# Battery_Charging_Circuit.net
KiCad netlist of a schematic drawn in Altium Designer
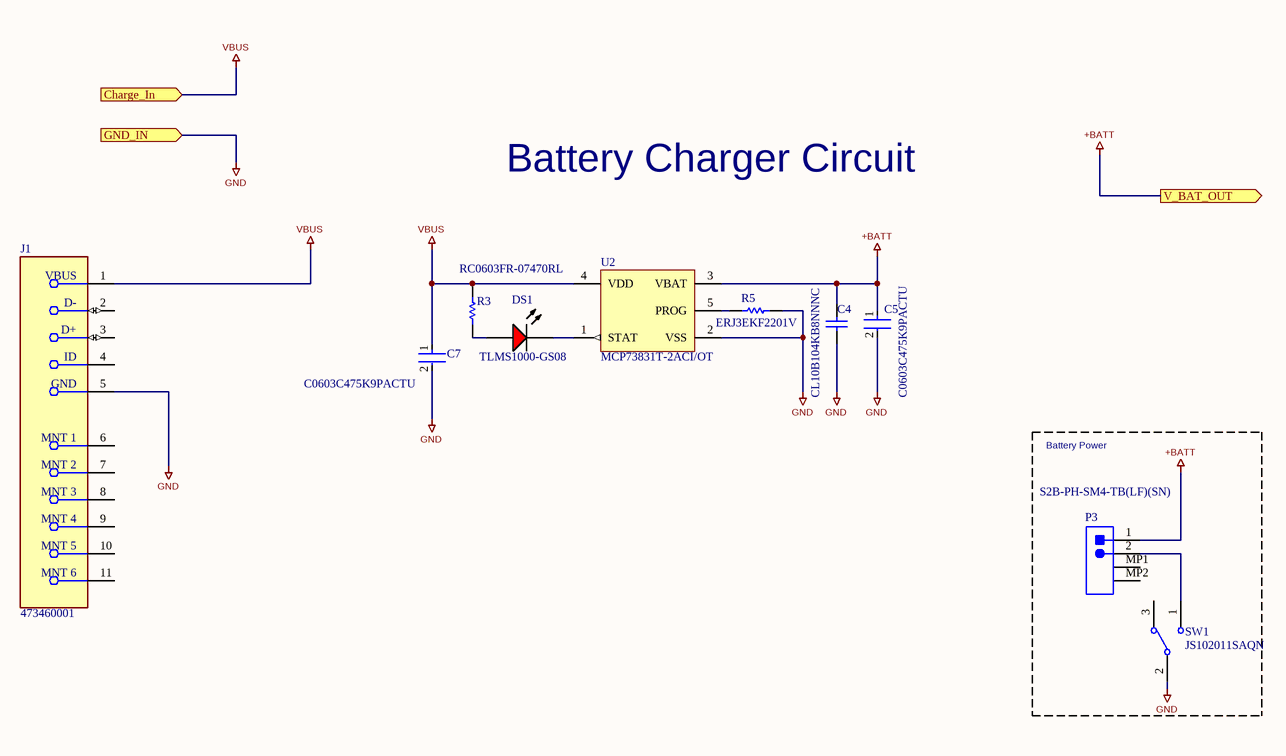
[diagram p0: Battery Charging Circuit.SchDoc]

(export (version "E")
  (design (tool "Eeschema 10.0.6"))
  (components
    (comp (ref "C4")
      (value "CL10B104KB8NNNC")
      (footprint "SAMS-C0603-2_M")
      (description "Multi-layer Ceramic Capacitor, -55 to 125 degC, 2-Pin SMD (0603), RoHS, Tape and Reel")
      (fields (field (name "MANUFACTURER") "Samsung Electro-Mechanics"))
      (libsource (lib "Altium Content Vault") (part "CAP-NP-2"))
    )
    (comp (ref "C5")
      (value "C0603C475K9PACTU")
      (footprint "FP-C0603-CG-MFG")
      (description "CAP CER 4.7UF 6.3V X5R 0603")
      (fields (field (name "TOLERANCE") "10%") (field (name "MANUFACTURER") "Kemet"))
      (libsource (lib "Altium Content Vault") (part "11868f565c42a9108669ba33697ecf6"))
    )
    (comp (ref "C7")
      (value "C0603C475K9PACTU")
      (footprint "FP-C0603-CG-MFG")
      (description "CAP CER 4.7UF 6.3V X5R 0603")
      (fields (field (name "TOLERANCE") "10%") (field (name "MANUFACTURER") "Kemet"))
      (libsource (lib "Altium Content Vault") (part "11868f565c42a9108669ba33697ecf6"))
    )
    (comp (ref "DS1")
      (value "TLMS1000-GS08")
      (footprint "VISH-TLMS1000_V")
      (description "Low Current LED, 40 mW, 1.8 V, -40 to 100 degC, 2-Pin SMD (0603), RoHS, Tape and Reel")
      (fields (field (name "MANUFACTURER") "Vishay"))
      (libsource (lib "Altium Content Vault") (part "LED-RED-AK-2"))
    )
    (comp (ref "J1")
      (value "473460001")
      (footprint "FP-473460001-MFG")
      (description "CONN RCPT USB2.0 MICRO B SMD R/A")
      (fields
        (field (name "OCTOPART") "https://octopart.com/47346-0001-molex-7164928")
        (field (name "MANUFACTURER") "Molex")
      )
      (libsource (lib "Altium Content Vault") (part "53ae1f1d9b557310b43ca686e5bb76a"))
    )
    (comp (ref "P3")
      (value "S2B-PH-SM4-TB(LF)(SN)")
      (footprint "JST- S2B-PH-SM4-TB(LF)(SN)-2_V")
      (description "Male Header, Pitch 2 mm, 1 x 2 Position, Height 5.5 mm, -25 to 85 degC, RoHS, Tape and Reel")
      (libsource (lib "Altium Content Vault") (part "CN-1P-2M-R2"))
    )
    (comp (ref "R3")
      (value "RC0603FR-07470RL")
      (footprint "RESC1608X55X25LL10T15")
      (libsource (lib "Altium Content Vault") (part "RES-2"))
    )
    (comp (ref "R5")
      (value "ERJ3EKF2201V")
      (footprint "RESC1608X55X30LL15T15")
      (fields (field (name "MANUFACTURER") "Panasonic"))
      (libsource (lib "Altium Content Vault") (part "RES"))
    )
    (comp (ref "SW1")
      (value "JS102011SAQN")
      (footprint "CKCP-JS102011SAQN-3_V")
      (description "Sub-Miniature Slide Switch, SPDT, -40 to 85 degC, 3-Pin SMD, RoHS, Tape and Reel")
      (fields (field (name "MANUFACTURER") "C&K Components"))
      (libsource (lib "Altium Content Vault") (part "SW-SPDT-3"))
    )
    (comp (ref "U2")
      (value "MCP73831T-2ACI/OT")
      (footprint "SOT-23-OT5_M")
      (libsource (lib "Altium Content Vault") (part "PM-BM-MCP73831-SOT5"))
    )
  )
  (nets
    (net (code "1") (name "+BATT") (class "Default")
      (node (ref "C4") (pin "2") (pinfunction "2_2") (pintype "passive"))
      (node (ref "C5") (pin "1") (pinfunction "1_1") (pintype "passive"))
      (node (ref "P3") (pin "1") (pinfunction "1_1") (pintype "passive"))
      (node (ref "U2") (pin "3") (pinfunction "VBAT_3") (pintype "power_in"))
    )
    (net (code "2") (name "GND") (class "Default")
      (node (ref "C4") (pin "1") (pinfunction "1_1") (pintype "passive"))
      (node (ref "C5") (pin "2") (pinfunction "2_2") (pintype "passive"))
      (node (ref "C7") (pin "2") (pinfunction "2_2") (pintype "passive"))
      (node (ref "J1") (pin "5") (pinfunction "GND_5") (pintype "power_in"))
      (node (ref "R5") (pin "1") (pinfunction "1_1") (pintype "passive"))
      (node (ref "SW1") (pin "2") (pinfunction "2_2") (pintype "passive"))
      (node (ref "U2") (pin "2") (pinfunction "VSS_2") (pintype "power_in"))
    )
    (net (code "3") (name "Net-(DS1-A)") (class "Default")
      (node (ref "DS1") (pin "1") (pinfunction "A_1") (pintype "passive"))
      (node (ref "R3") (pin "1") (pinfunction "1_1") (pintype "passive"))
    )
    (net (code "4") (name "Net-(DS1-K)") (class "Default")
      (node (ref "DS1") (pin "2") (pinfunction "K_2") (pintype "passive"))
      (node (ref "U2") (pin "1") (pinfunction "STAT_1") (pintype "output"))
    )
    (net (code "5") (name "Net-(P3-Pad2)") (class "Default")
      (node (ref "P3") (pin "2") (pinfunction "2_2") (pintype "passive"))
      (node (ref "SW1") (pin "1") (pinfunction "1_1") (pintype "passive"))
    )
    (net (code "6") (name "Net-(U2-PROG)") (class "Default")
      (node (ref "R5") (pin "2") (pinfunction "2_2") (pintype "passive"))
      (node (ref "U2") (pin "5") (pinfunction "PROG_5") (pintype "passive"))
    )
    (net (code "7") (name "VBUS") (class "Default")
      (node (ref "C7") (pin "1") (pinfunction "1_1") (pintype "passive"))
      (node (ref "J1") (pin "1") (pinfunction "VBUS_1") (pintype "power_in"))
      (node (ref "R3") (pin "2") (pinfunction "2_2") (pintype "passive"))
      (node (ref "U2") (pin "4") (pinfunction "VDD_4") (pintype "power_in"))
    )
    (net (code "8") (name "unconnected-(J1-D+-Pad3)") (class "Default")
      (node (ref "J1") (pin "3") (pinfunction "D+_3") (pintype "bidirectional"))
    )
    (net (code "9") (name "unconnected-(J1-D--Pad2)") (class "Default")
      (node (ref "J1") (pin "2") (pinfunction "D-_2") (pintype "bidirectional"))
    )
    (net (code "10") (name "unconnected-(J1-ID-Pad4)") (class "Default")
      (node (ref "J1") (pin "4") (pinfunction "ID_4") (pintype "passive"))
    )
    (net (code "11") (name "unconnected-(J1-MNT_1-Pad6)") (class "Default")
      (node (ref "J1") (pin "6") (pinfunction "MNT_1_6") (pintype "passive"))
    )
    (net (code "12") (name "unconnected-(J1-MNT_2-Pad7)") (class "Default")
      (node (ref "J1") (pin "7") (pinfunction "MNT_2_7") (pintype "passive"))
    )
    (net (code "13") (name "unconnected-(J1-MNT_3-Pad8)") (class "Default")
      (node (ref "J1") (pin "8") (pinfunction "MNT_3_8") (pintype "passive"))
    )
    (net (code "14") (name "unconnected-(J1-MNT_4-Pad9)") (class "Default")
      (node (ref "J1") (pin "9") (pinfunction "MNT_4_9") (pintype "passive"))
    )
    (net (code "15") (name "unconnected-(J1-MNT_5-Pad10)") (class "Default")
      (node (ref "J1") (pin "10") (pinfunction "MNT_5_10") (pintype "passive"))
    )
    (net (code "16") (name "unconnected-(J1-MNT_6-Pad11)") (class "Default")
      (node (ref "J1") (pin "11") (pinfunction "MNT_6_11") (pintype "passive"))
    )
    (net (code "17") (name "unconnected-(P3-PadMP1)") (class "Default")
      (node (ref "P3") (pin "MP1") (pinfunction "MP1_MP1") (pintype "passive"))
    )
    (net (code "18") (name "unconnected-(P3-PadMP2)") (class "Default")
      (node (ref "P3") (pin "MP2") (pinfunction "MP2_MP2") (pintype "passive"))
    )
    (net (code "19") (name "unconnected-(SW1-Pad3)") (class "Default")
      (node (ref "SW1") (pin "3") (pinfunction "3_3") (pintype "passive"))
    )
  )
)
